# Sheet1.net
KiCad netlist of a schematic drawn in Altium Designer
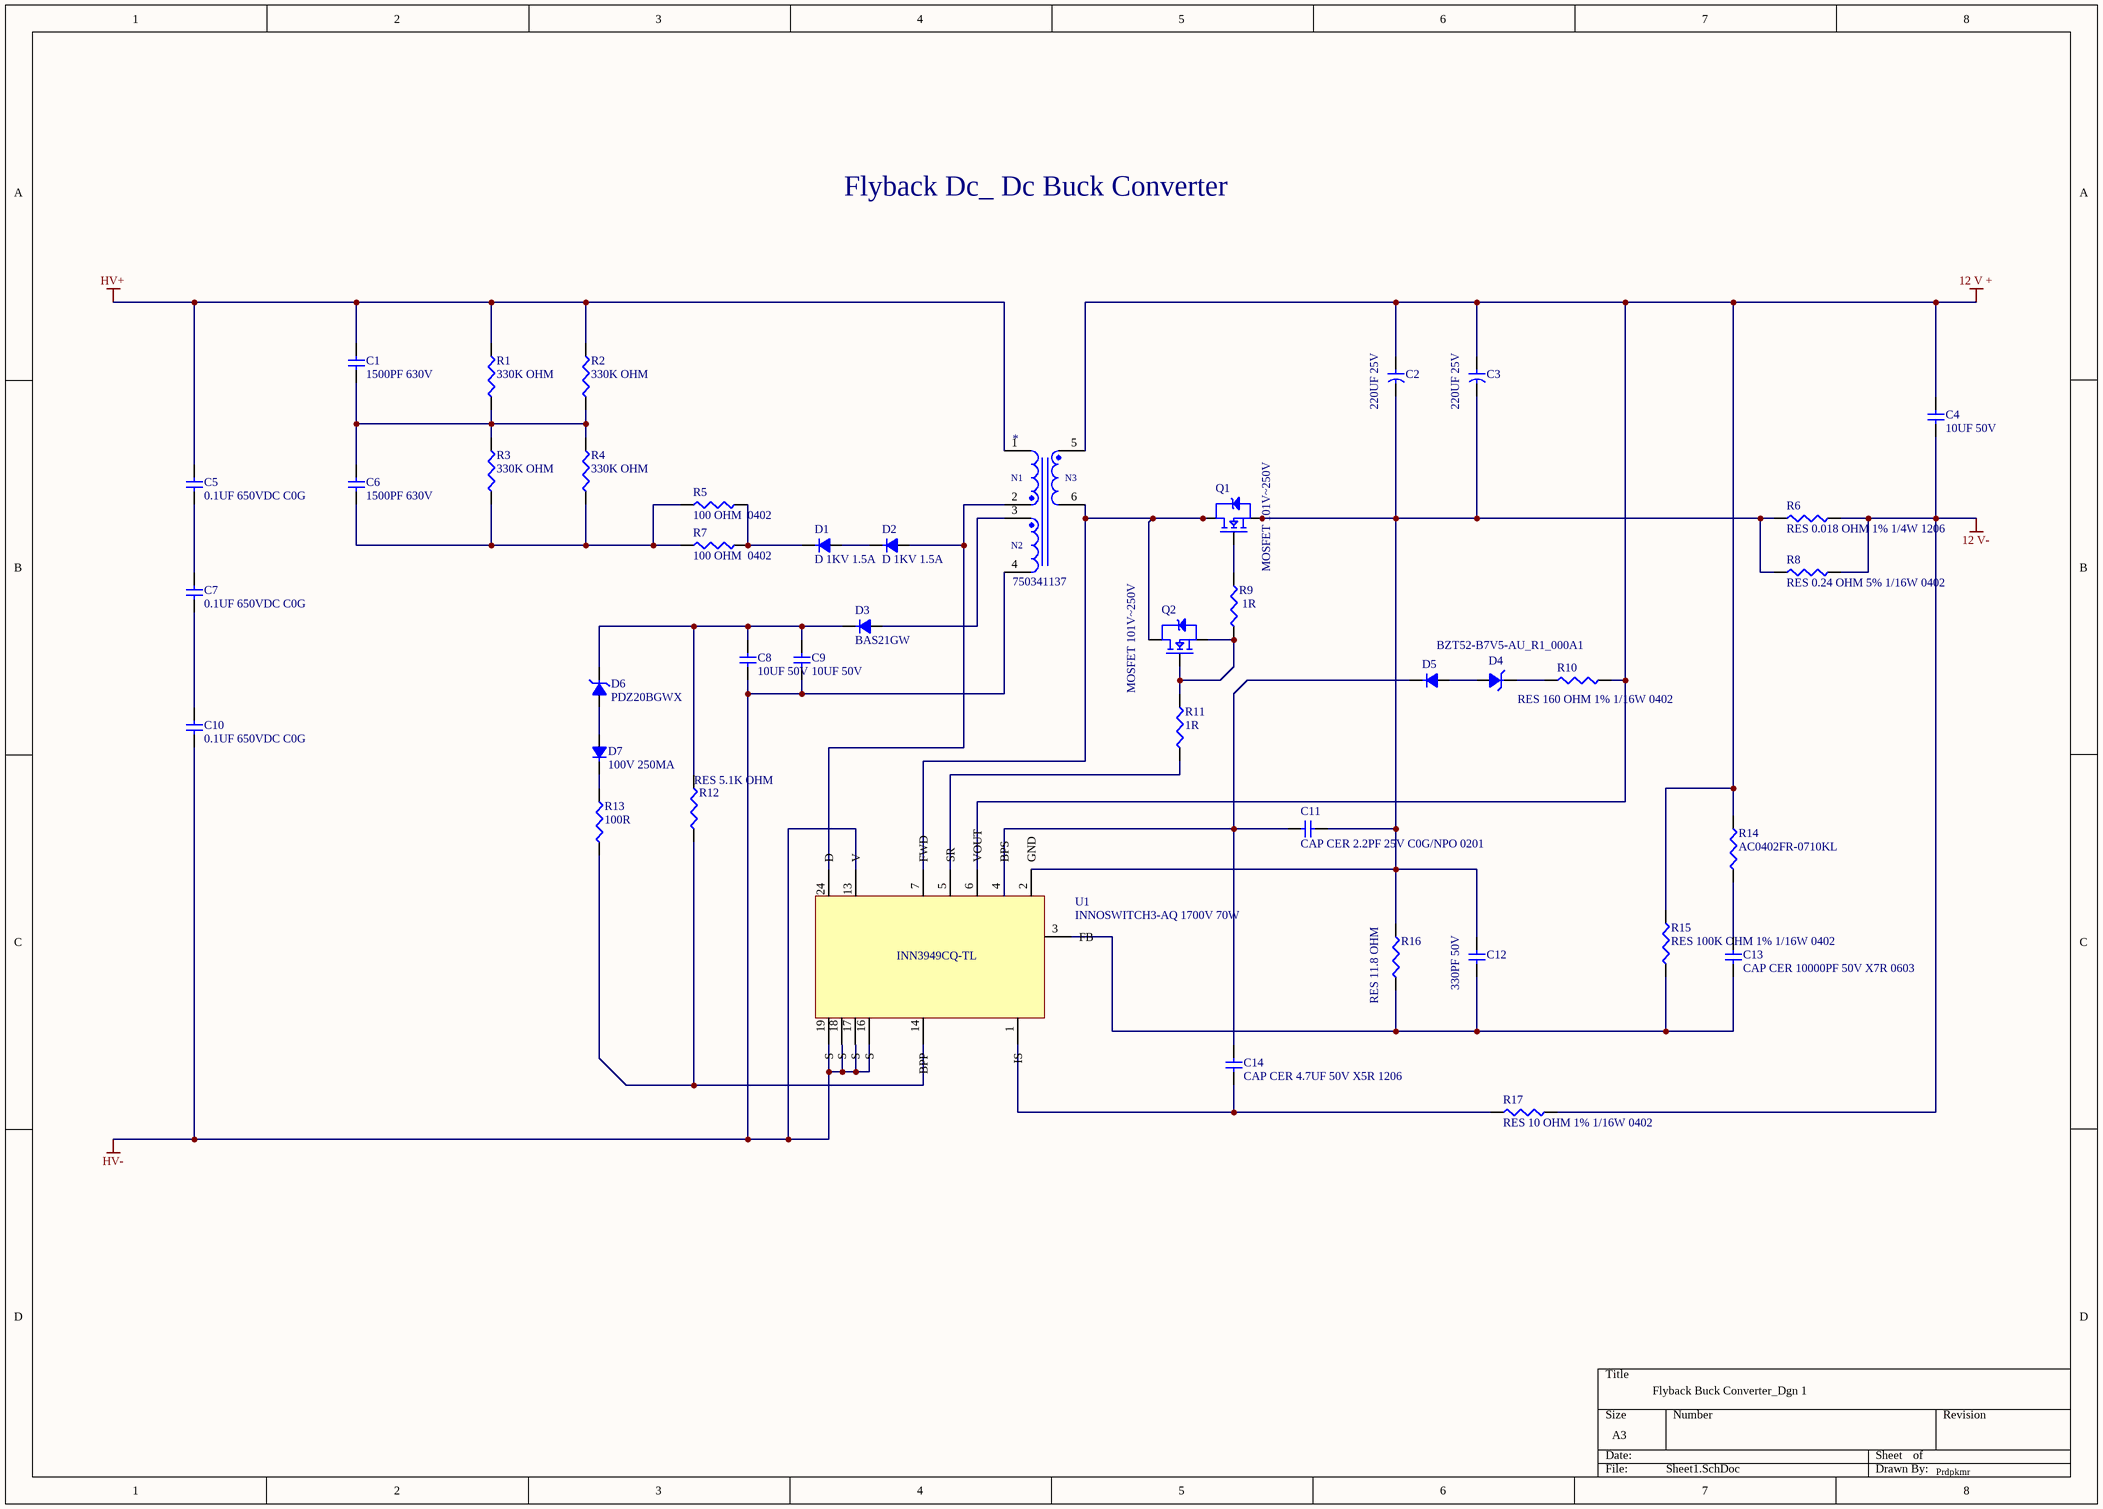
[diagram p0: Sheet1.SchDoc]

(export (version "E")
  (design (tool "Eeschema 10.0.6"))
  (components
    (comp (ref "*")
      (value "750341137")
      (footprint "ERI25/10/18_250-1446")
      (description "Transformer 480UH SMD")
      (fields (field (name "MANUFACTURER") "Wurth Electronics"))
      (libsource (lib "Schlib1") (part "750341137"))
    )
    (comp (ref "C1")
      (value "1500PF 630V")
      (description "1500 pF ±5% 630V Ceramic Capacitor C0G, NP0 1206 (3216 Metric)")
      (fields
        (field (name "MANUFACTURER") "TDK")
        (field (name "MANUFACTURER PART NUMBER") "CGA5H4C0G2J152J115AA")
      )
      (libsource (lib "Schlib1") (part "CGA5H4C0G2J152J115AA"))
    )
    (comp (ref "C2")
      (value "220UF 25V")
      (description "220 µF 25 V Aluminum - Polymer Capacitors Radial, Can - SMD 15mOhm 2000 Hrs @ 105°C")
      (fields
        (field (name "MANUFACTURER") "Wurth Electronics")
        (field (name "MANUFACTURER PART NUMBER") "875075561008")
      )
      (libsource (lib "Schlib1") (part "875075561008"))
    )
    (comp (ref "C3")
      (value "220UF 25V")
      (description "220 µF 25 V Aluminum - Polymer Capacitors Radial, Can - SMD 15mOhm 2000 Hrs @ 105°C")
      (fields
        (field (name "MANUFACTURER") "Wurth Electronics")
        (field (name "MANUFACTURER PART NUMBER") "875075561008")
      )
      (libsource (lib "Schlib1") (part "875075561008"))
    )
    (comp (ref "C4")
      (value "10UF 50V")
      (description "10 µF -20%, +80% 50V Ceramic Capacitor Y5V (F) 1210 (3225 Metric)")
      (fields
        (field (name "MANUFACTURER") "Yageo")
        (field (name "MANUFACTURER PART NUMBER") "CC1210ZKY5V9BB106")
      )
      (libsource (lib "Schlib1") (part "CC1210ZKY5V9BB106"))
    )
    (comp (ref "C5")
      (value "0.1UF 650VDC C0G")
      (description "0.1 µF ±10% 650V Ceramic Capacitor C0G, NP0 2220 (5750 Metric)")
      (fields
        (field (name "MANUFACTURER") "KEMET")
        (field (name "MANUFACTURER PART NUMBER") "CKC21C104KWGACAUTO")
      )
      (libsource (lib "Schlib1") (part "CKC21C104KWGACAUTO"))
    )
    (comp (ref "C6")
      (value "1500PF 630V")
      (description "1500 pF ±5% 630V Ceramic Capacitor C0G, NP0 1206 (3216 Metric)")
      (fields
        (field (name "MANUFACTURER") "TDK")
        (field (name "MANUFACTURER PART NUMBER") "CGA5H4C0G2J152J115AA")
      )
      (libsource (lib "Schlib1") (part "CGA5H4C0G2J152J115AA"))
    )
    (comp (ref "C7")
      (value "0.1UF 650VDC C0G")
      (description "0.1 µF ±10% 650V Ceramic Capacitor C0G, NP0 2220 (5750 Metric)")
      (fields
        (field (name "MANUFACTURER") "KEMET")
        (field (name "MANUFACTURER PART NUMBER") "CKC21C104KWGACAUTO")
      )
      (libsource (lib "Schlib1") (part "CKC21C104KWGACAUTO"))
    )
    (comp (ref "C8")
      (value "10UF 50V")
      (description "10 µF -20%, +80% 50V Ceramic Capacitor Y5V (F) 1210 (3225 Metric)")
      (fields
        (field (name "MANUFACTURER") "Yageo")
        (field (name "MANUFACTURER PART NUMBER") "CC1210ZKY5V9BB106")
      )
      (libsource (lib "Schlib1") (part "CC1210ZKY5V9BB106"))
    )
    (comp (ref "C9")
      (value "10UF 50V")
      (description "10 µF -20%, +80% 50V Ceramic Capacitor Y5V (F) 1210 (3225 Metric)")
      (fields
        (field (name "MANUFACTURER") "Yageo")
        (field (name "MANUFACTURER PART NUMBER") "CC1210ZKY5V9BB106")
      )
      (libsource (lib "Schlib1") (part "CC1210ZKY5V9BB106"))
    )
    (comp (ref "C10")
      (value "0.1UF 650VDC C0G")
      (description "0.1 µF ±10% 650V Ceramic Capacitor C0G, NP0 2220 (5750 Metric)")
      (fields
        (field (name "MANUFACTURER") "KEMET")
        (field (name "MANUFACTURER PART NUMBER") "CKC21C104KWGACAUTO")
      )
      (libsource (lib "Schlib1") (part "CKC21C104KWGACAUTO"))
    )
    (comp (ref "C11")
      (value "CAP CER 2.2PF 25V C0G/NPO 0201")
      (description "2.2 pF ±0.25pF 25V Ceramic Capacitor C0G, NP0 0201 (0603 Metric)")
      (fields
        (field (name "MANUFACTURER") "Yageo")
        (field (name "MANUFACTURER PART NUMBER") "CC0201CRNPO8BN2R2")
      )
      (libsource (lib "Schlib1") (part "CC0201CRNPO8BN2R2"))
    )
    (comp (ref "C12")
      (value "330PF 50V")
      (description "330 pF ±10% 50V Ceramic Capacitor X7R 0402 (1005 Metric)")
      (fields
        (field (name "MANUFACTURER") "Yageo")
        (field (name "MANUFACTURER PART NUMBER") "CC0402KRX7R9BB331")
      )
      (libsource (lib "Schlib1") (part "CC0402KRX7R9BB331"))
    )
    (comp (ref "C13")
      (value "CAP CER 10000PF 50V X7R 0603")
      (description "10000 pF ±10% 50V Ceramic Capacitor X7R 0603 (1608 Metric)")
      (fields
        (field (name "MANUFACTURER") "Yageo")
        (field (name "MANUFACTURER PART NUMBER") "CC0603KRX7R9BB103")
      )
      (libsource (lib "Schlib1") (part "CC0603KRX7R9BB103"))
    )
    (comp (ref "C14")
      (value "CAP CER 4.7UF 50V X5R 1206")
      (description "4.7 µF ±10% 50V Ceramic Capacitor X5R 1206 (3216 Metric)")
      (fields
        (field (name "MANUFACTURER") "Yageo")
        (field (name "MANUFACTURER PART NUMBER") "CC1206KKX5R9BB475")
      )
      (libsource (lib "Schlib1") (part "CC1206KKX5R9BB475"))
    )
    (comp (ref "D1")
      (value "D 1KV 1.5A")
      (description "Diode 1000 V 1.5A Surface Mount DO-214AC (SMA)")
      (fields
        (field (name "MANUFACTURER") "Vishay")
        (field (name "MANUFACTURER PART NUMBER") "BYG23MHE3_A/I")
      )
      (libsource (lib "Schlib1") (part "BYG23MHE3_A/I"))
    )
    (comp (ref "D2")
      (value "D 1KV 1.5A")
      (description "Diode 1000 V 1.5A Surface Mount DO-214AC (SMA)")
      (fields
        (field (name "MANUFACTURER") "Vishay")
        (field (name "MANUFACTURER PART NUMBER") "BYG23MHE3_A/I")
      )
      (libsource (lib "Schlib1") (part "BYG23MHE3_A/I"))
    )
    (comp (ref "D3")
      (value "BAS21GW")
      (description "Diode 200 V 225mA Surface Mount SOD-123")
      (fields (field (name "MANUFACTURER") "Nexperia") (field (name "MANUFACTURER PART NUMBER") "BAS21GWX"))
      (libsource (lib "Schlib1") (part "BAS21GWX"))
    )
    (comp (ref "D4")
      (value "BZT52-B7V5-AU_R1_000A1")
      (description "Zener Diode 7.5 V 410 mW ±2% Surface Mount SOD-123")
      (fields (field (name "MANUFACTURER") "Panjit"))
      (libsource (lib "Schlib1") (part "BZT52-B7V5-AU_R1_000A1"))
    )
    (comp (ref "D5")
      (value "~")
      (description "Diode 100 V 250mA Surface Mount SOD-323F")
      (fields (field (name "MANUFACTURER") "Nexperia") (field (name "MANUFACTURER PART NUMBER") "BAS16J,115"))
      (libsource (lib "Schlib1") (part "BAS16J,115"))
    )
    (comp (ref "D6")
      (value "PDZ20BGWX")
      (description "DIODE ZENER 20V 365MW SOD123")
      (fields (field (name "MANUFACTURER") "Nexperia"))
      (libsource (lib "Schlib1") (part "PDZ20BGWX"))
    )
    (comp (ref "D7")
      (value "100V 250MA")
      (description "Diode 100 V 250mA Surface Mount SOD-323F")
      (fields (field (name "MANUFACTURER") "Nexperia") (field (name "MANUFACTURER PART NUMBER") "BAS16J,115"))
      (libsource (lib "Schlib1") (part "BAS16J,115"))
    )
    (comp (ref "Q1")
      (value "MOSFET 101V~250V")
      (fields
        (field (name "MANUFACTURER") "Diodes")
        (field (name "MANUFACTURER PART NUMBER") "DMTH15H017LPSWQ-13")
      )
      (libsource (lib "Schlib1") (part "DMTH15H017LPSWQ-13"))
    )
    (comp (ref "Q2")
      (value "MOSFET 101V~250V")
      (fields
        (field (name "MANUFACTURER") "Diodes")
        (field (name "MANUFACTURER PART NUMBER") "DMTH15H017LPSWQ-13")
      )
      (libsource (lib "Schlib1") (part "DMTH15H017LPSWQ-13"))
    )
    (comp (ref "R1")
      (value "330K OHM")
      (description "330 kOhms ±1% 0.35W Chip Resistor 1210 (3225 Metric) High Voltage Thick Film")
      (fields
        (field (name "MANUFACTURER") "Vishay")
        (field (name "MANUFACTURER PART NUMBER") "CRMV1210AF330KFKEF")
      )
      (libsource (lib "Schlib1") (part "CRMV1210AF330KFKEF"))
    )
    (comp (ref "R2")
      (value "330K OHM")
      (description "330 kOhms ±1% 0.35W Chip Resistor 1210 (3225 Metric) High Voltage Thick Film")
      (fields
        (field (name "MANUFACTURER") "Vishay")
        (field (name "MANUFACTURER PART NUMBER") "CRMV1210AF330KFKEF")
      )
      (libsource (lib "Schlib1") (part "CRMV1210AF330KFKEF"))
    )
    (comp (ref "R3")
      (value "330K OHM")
      (description "330 kOhms ±1% 0.35W Chip Resistor 1210 (3225 Metric) High Voltage Thick Film")
      (fields
        (field (name "MANUFACTURER") "Vishay")
        (field (name "MANUFACTURER PART NUMBER") "CRMV1210AF330KFKEF")
      )
      (libsource (lib "Schlib1") (part "CRMV1210AF330KFKEF"))
    )
    (comp (ref "R4")
      (value "330K OHM")
      (description "330 kOhms ±1% 0.35W Chip Resistor 1210 (3225 Metric) High Voltage Thick Film")
      (fields
        (field (name "MANUFACTURER") "Vishay")
        (field (name "MANUFACTURER PART NUMBER") "CRMV1210AF330KFKEF")
      )
      (libsource (lib "Schlib1") (part "CRMV1210AF330KFKEF"))
    )
    (comp (ref "R5")
      (value "100 OHM  0402")
      (description "100 Ohms ±1% 0.05W, 1/20W Chip Resistor 0402 (1005 Metric) Military Thick Film")
      (fields
        (field (name "MANUFACTURER") "Vishay Dale")
        (field (name "MANUFACTURER PART NUMBER") "M55342K11B100DRS3")
      )
      (libsource (lib "Schlib1") (part "M55342K11B100DRS3"))
    )
    (comp (ref "R6")
      (value "RES 0.018 OHM 1% 1/4W 1206")
      (description "Res Thick Film 1206 0.018 Ohm 1% 1/4W ±1500ppm/°C Molded SMD SMD Paper T/R")
      (fields
        (field (name "MANUFACTURER") "Yageo")
        (field (name "MANUFACTURER PART NUMBER") "RL1206FR-070R018L")
      )
      (libsource (lib "Schlib1") (part "RL1206FR-070R018L"))
    )
    (comp (ref "R7")
      (value "100 OHM  0402")
      (description "100 Ohms ±1% 0.05W, 1/20W Chip Resistor 0402 (1005 Metric) Military Thick Film")
      (fields
        (field (name "MANUFACTURER") "Vishay Dale")
        (field (name "MANUFACTURER PART NUMBER") "M55342K11B100DRS3")
      )
      (libsource (lib "Schlib1") (part "M55342K11B100DRS3"))
    )
    (comp (ref "R8")
      (value "RES 0.24 OHM 5% 1/16W 0402")
      (description "Current Sensor-Low TCR Chip Resistor Thick Film 0402 240mOhm 5% Paper T/R")
      (fields
        (field (name "MANUFACTURER") "Yageo")
        (field (name "MANUFACTURER PART NUMBER") "PT0402JR-070R24L")
      )
      (libsource (lib "Schlib1") (part "PT0402JR-070R24L"))
    )
    (comp (ref "R9")
      (value "1R")
      (fields
        (field (name "MANUFACTURER") "Bourns")
        (field (name "MANUFACTURER PART NUMBER") "CR0402AF/-1R00GAS")
        (field (name "TOLERANCE") "1%")
      )
      (libsource (lib "Schlib1") (part "CR0402AF/-1R00GAS"))
    )
    (comp (ref "R10")
      (value "RES 160 OHM 1% 1/16W 0402")
      (description "SMD Chip Resistor, 160 Ohm, ï¿½ 1%, 63 mW, 0402 [1005 Metric], Thick Film, General Purpose")
      (fields
        (field (name "MANUFACTURER") "Yageo")
        (field (name "MANUFACTURER PART NUMBER") "RC0402FR-07160RL")
      )
      (libsource (lib "Schlib1") (part "RC0402FR-07160RL"))
    )
    (comp (ref "R11")
      (value "1R")
      (fields
        (field (name "MANUFACTURER") "Bourns")
        (field (name "MANUFACTURER PART NUMBER") "CR0402AF/-1R00GAS")
        (field (name "TOLERANCE") "1%")
      )
      (libsource (lib "Schlib1") (part "CR0402AF/-1R00GAS"))
    )
    (comp (ref "R12")
      (value "RES 5.1K OHM")
      (description "5.1 kOhms ±1% 0.063W, 1/16W Chip Resistor 0402 (1005 Metric) Moisture Resistant Thick Film")
      (fields
        (field (name "MANUFACTURER") "Yageo")
        (field (name "MANUFACTURER PART NUMBER") "RC0402FR-075K1L")
      )
      (libsource (lib "Schlib1") (part "RC0402FR-075K1L"))
    )
    (comp (ref "R13")
      (value "100R")
      (description "100 Ohms ±0.1% 0.063W, 1/16W Chip Resistor 0402 (1005 Metric) Thin Film")
      (fields
        (field (name "MANUFACTURER") "Yageo")
        (field (name "MANUFACTURER PART NUMBER") "RT0402BRD07100RL")
      )
      (libsource (lib "Schlib1") (part "RT0402BRD07100RL"))
    )
    (comp (ref "R14")
      (value "AC0402FR-0710KL")
      (description "SMD Chip Resistor, 10 kOhm, ï¿½ 1%, 62.5 mW, 0402 [1005 Metric], Thick Film, General Purpose")
      (fields (field (name "MANUFACTURER") "Yageo") (field (name "TOLERANCE") "1%"))
      (libsource (lib "Schlib1") (part "AC0402FR-0710KL"))
    )
    (comp (ref "R15")
      (value "RES 100K OHM 1% 1/16W 0402")
      (description "Res General Purpose Thick Film 0402 100K Ohm 1% 1/16W ±100ppm/°C Molded SMD Paper T/R")
      (fields
        (field (name "MANUFACTURER") "Yageo")
        (field (name "MANUFACTURER PART NUMBER") "RC0402FR-07100KL")
      )
      (libsource (lib "Schlib1") (part "RC0402FR-07100KL"))
    )
    (comp (ref "R16")
      (value "RES 11.8 OHM")
      (description "Res Thick Film 0402 11.8 Ohm 1% 0.063W(1/16W) ±100ppm/C Pad SMD T/R")
      (fields
        (field (name "MANUFACTURER") "Yageo")
        (field (name "MANUFACTURER PART NUMBER") "RC0402FR-0711R8L")
      )
      (libsource (lib "Schlib1") (part "RC0402FR-0711R8L"))
    )
    (comp (ref "R17")
      (value "RES 10 OHM 1% 1/16W 0402")
      (description "Res Thick Film 0402 11.8 Ohm 1% 0.063W(1/16W) ±100ppm/C Pad SMD T/R")
      (fields
        (field (name "MANUFACTURER") "Yageo")
        (field (name "MANUFACTURER PART NUMBER") "RC0402FR-0710RL")
      )
      (libsource (lib "Schlib1") (part "RC0402FR-0710RL"))
    )
    (comp (ref "U1")
      (value "INNOSWITCH3-AQ 1700V 70W")
      (description "Ac-Dc Conv, Flyback, -40 To 150Deg C Rohs Compliant: Yes ¦Power Integrations INN3949CQ-TL")
      (fields
        (field (name "MANUFACTURER") "Power Integrations")
        (field (name "MANUFACTURER PART NUMBER") "INN3949CQ-TL")
      )
      (libsource (lib "Schlib1") (part "INN3949CQ-TL"))
    )
  )
  (nets
    (net (code "1") (name "12 V +") (class "Default")
      (node (ref "*") (pin "5") (pinfunction "5_5") (pintype "passive"))
      (node (ref "C2") (pin "1") (pinfunction "1_1") (pintype "passive"))
      (node (ref "C3") (pin "1") (pinfunction "1_1") (pintype "passive"))
      (node (ref "C4") (pin "2") (pinfunction "_2_2") (pintype "passive"))
      (node (ref "R10") (pin "2") (pinfunction "2_2") (pintype "passive"))
      (node (ref "R14") (pin "2") (pinfunction "2_2") (pintype "passive"))
      (node (ref "R15") (pin "2") (pinfunction "2_2") (pintype "passive"))
    )
    (net (code "2") (name "12 V-") (class "Default")
      (node (ref "C4") (pin "1") (pinfunction "1_1") (pintype "passive"))
      (node (ref "R17") (pin "2") (pinfunction "2_2") (pintype "passive"))
      (node (ref "R6") (pin "2") (pinfunction "2_2") (pintype "passive"))
      (node (ref "R8") (pin "2") (pinfunction "2_2") (pintype "passive"))
    )
    (net (code "3") (name "HV+") (class "Default")
      (node (ref "*") (pin "1") (pinfunction "1_1") (pintype "passive"))
      (node (ref "C1") (pin "2") (pinfunction "_2_2") (pintype "passive"))
      (node (ref "C5") (pin "2") (pinfunction "_2_2") (pintype "passive"))
      (node (ref "R1") (pin "2") (pinfunction "2_2") (pintype "passive"))
      (node (ref "R2") (pin "2") (pinfunction "2_2") (pintype "passive"))
    )
    (net (code "4") (name "HV-") (class "Default")
      (node (ref "*") (pin "4") (pinfunction "4_4") (pintype "passive"))
      (node (ref "C10") (pin "1") (pinfunction "1_1") (pintype "passive"))
      (node (ref "C8") (pin "1") (pinfunction "1_1") (pintype "passive"))
      (node (ref "C9") (pin "1") (pinfunction "1_1") (pintype "passive"))
    )
    (net (code "5") (name "Net-(*-Pad2)") (class "Default")
      (node (ref "*") (pin "2") (pinfunction "2_2") (pintype "passive"))
      (node (ref "D2") (pin "1") (pinfunction "1_1") (pintype "passive"))
    )
    (net (code "6") (name "Net-(*-Pad3)") (class "Default")
      (node (ref "*") (pin "3") (pinfunction "3_3") (pintype "passive"))
      (node (ref "D3") (pin "1") (pinfunction "1_1") (pintype "passive"))
    )
    (net (code "7") (name "Net-(*-Pad6)") (class "Default")
      (node (ref "*") (pin "6") (pinfunction "6_6") (pintype "passive"))
      (node (ref "Q1") (pin "2") (pinfunction "2_2") (pintype "passive"))
      (node (ref "Q2") (pin "2") (pinfunction "2_2") (pintype "passive"))
    )
    (net (code "8") (name "Net-(C6-Pad1)") (class "Default")
      (node (ref "C6") (pin "1") (pinfunction "1_1") (pintype "passive"))
      (node (ref "R3") (pin "1") (pinfunction "1_1") (pintype "passive"))
      (node (ref "R4") (pin "1") (pinfunction "1_1") (pintype "passive"))
      (node (ref "R5") (pin "1") (pinfunction "1_1") (pintype "passive"))
      (node (ref "R7") (pin "1") (pinfunction "1_1") (pintype "passive"))
    )
    (net (code "9") (name "Net-(C6-_2)") (class "Default")
      (node (ref "C1") (pin "1") (pinfunction "1_1") (pintype "passive"))
      (node (ref "C6") (pin "2") (pinfunction "_2_2") (pintype "passive"))
      (node (ref "R1") (pin "1") (pinfunction "1_1") (pintype "passive"))
      (node (ref "R2") (pin "1") (pinfunction "1_1") (pintype "passive"))
      (node (ref "R3") (pin "2") (pinfunction "2_2") (pintype "passive"))
      (node (ref "R4") (pin "2") (pinfunction "2_2") (pintype "passive"))
    )
    (net (code "10") (name "Net-(C7-_2)") (class "Default")
      (node (ref "C5") (pin "1") (pinfunction "1_1") (pintype "passive"))
      (node (ref "C7") (pin "2") (pinfunction "_2_2") (pintype "passive"))
    )
    (net (code "11") (name "Net-(C8-_2)") (class "Default")
      (node (ref "C8") (pin "2") (pinfunction "_2_2") (pintype "passive"))
      (node (ref "C9") (pin "2") (pinfunction "_2_2") (pintype "passive"))
      (node (ref "D3") (pin "2") (pinfunction "2_2") (pintype "passive"))
      (node (ref "D6") (pin "2") (pinfunction "2_2") (pintype "passive"))
      (node (ref "R12") (pin "2") (pinfunction "2_2") (pintype "passive"))
    )
    (net (code "12") (name "Net-(C10-_2)") (class "Default")
      (node (ref "C10") (pin "2") (pinfunction "_2_2") (pintype "passive"))
      (node (ref "C7") (pin "1") (pinfunction "1_1") (pintype "passive"))
    )
    (net (code "13") (name "Net-(C11-_2)") (class "Default")
      (node (ref "C11") (pin "2") (pinfunction "_2_2") (pintype "passive"))
      (node (ref "C12") (pin "2") (pinfunction "_2_2") (pintype "passive"))
      (node (ref "C2") (pin "2") (pinfunction "_2_2") (pintype "passive"))
      (node (ref "C3") (pin "2") (pinfunction "_2_2") (pintype "passive"))
      (node (ref "Q1") (pin "3") (pinfunction "3_3") (pintype "passive"))
      (node (ref "R16") (pin "2") (pinfunction "2_2") (pintype "passive"))
      (node (ref "R6") (pin "1") (pinfunction "1_1") (pintype "passive"))
      (node (ref "R8") (pin "1") (pinfunction "1_1") (pintype "passive"))
    )
    (net (code "14") (name "Net-(C12-Pad1)") (class "Default")
      (node (ref "C12") (pin "1") (pinfunction "1_1") (pintype "passive"))
      (node (ref "C13") (pin "1") (pinfunction "1_1") (pintype "passive"))
      (node (ref "R15") (pin "1") (pinfunction "1_1") (pintype "passive"))
      (node (ref "R16") (pin "1") (pinfunction "1_1") (pintype "passive"))
    )
    (net (code "15") (name "Net-(C13-_2)") (class "Default")
      (node (ref "C13") (pin "2") (pinfunction "_2_2") (pintype "passive"))
      (node (ref "R14") (pin "1") (pinfunction "1_1") (pintype "passive"))
    )
    (net (code "16") (name "Net-(C14-Pad1)") (class "Default")
      (node (ref "C14") (pin "1") (pinfunction "1_1") (pintype "passive"))
      (node (ref "R17") (pin "1") (pinfunction "1_1") (pintype "passive"))
    )
    (net (code "17") (name "Net-(C14-_2)") (class "Default")
      (node (ref "C11") (pin "1") (pinfunction "1_1") (pintype "passive"))
      (node (ref "C14") (pin "2") (pinfunction "_2_2") (pintype "passive"))
      (node (ref "D5") (pin "2") (pinfunction "2_2") (pintype "passive"))
      (node (ref "U1") (pin "4") (pinfunction "BPS_4") (pintype "passive"))
    )
    (net (code "18") (name "Net-(D1-Pad1)") (class "Default")
      (node (ref "D1") (pin "1") (pinfunction "1_1") (pintype "passive"))
      (node (ref "D2") (pin "2") (pinfunction "2_2") (pintype "passive"))
    )
    (net (code "19") (name "Net-(D1-Pad2)") (class "Default")
      (node (ref "D1") (pin "2") (pinfunction "2_2") (pintype "passive"))
      (node (ref "R5") (pin "2") (pinfunction "2_2") (pintype "passive"))
      (node (ref "R7") (pin "2") (pinfunction "2_2") (pintype "passive"))
    )
    (net (code "20") (name "Net-(D4-Pad1)") (class "Default")
      (node (ref "D4") (pin "1") (pinfunction "1_1") (pintype "passive"))
      (node (ref "D5") (pin "1") (pinfunction "1_1") (pintype "passive"))
    )
    (net (code "21") (name "Net-(D4-Pad2)") (class "Default")
      (node (ref "D4") (pin "2") (pinfunction "2_2") (pintype "passive"))
      (node (ref "R10") (pin "1") (pinfunction "1_1") (pintype "passive"))
    )
    (net (code "22") (name "Net-(D6-Pad1)") (class "Default")
      (node (ref "D6") (pin "1") (pinfunction "1_1") (pintype "passive"))
      (node (ref "D7") (pin "1") (pinfunction "1_1") (pintype "passive"))
    )
    (net (code "23") (name "Net-(D7-Pad2)") (class "Default")
      (node (ref "D7") (pin "2") (pinfunction "2_2") (pintype "passive"))
      (node (ref "R13") (pin "2") (pinfunction "2_2") (pintype "passive"))
    )
    (net (code "24") (name "Net-(Q1-Pad1)") (class "Default")
      (node (ref "Q1") (pin "1") (pinfunction "1_1") (pintype "passive"))
      (node (ref "R9") (pin "2") (pinfunction "2_2") (pintype "passive"))
    )
    (net (code "25") (name "Net-(Q2-Pad1)") (class "Default")
      (node (ref "Q2") (pin "1") (pinfunction "1_1") (pintype "passive"))
      (node (ref "Q2") (pin "3") (pinfunction "3_3") (pintype "passive"))
      (node (ref "R11") (pin "2") (pinfunction "2_2") (pintype "passive"))
      (node (ref "R9") (pin "1") (pinfunction "1_1") (pintype "passive"))
    )
    (net (code "26") (name "Net-(R12-Pad1)") (class "Default")
      (node (ref "R12") (pin "1") (pinfunction "1_1") (pintype "passive"))
      (node (ref "R13") (pin "1") (pinfunction "1_1") (pintype "passive"))
    )
    (net (code "27") (name "unconnected-(R11-Pad1)") (class "Default")
      (node (ref "R11") (pin "1") (pinfunction "1_1") (pintype "passive"))
    )
    (net (code "28") (name "unconnected-(U1-BPP-Pad14)") (class "Default")
      (node (ref "U1") (pin "14") (pinfunction "BPP_14") (pintype "passive"))
    )
    (net (code "29") (name "unconnected-(U1-D-Pad24)") (class "Default")
      (node (ref "U1") (pin "24") (pinfunction "D_24") (pintype "passive"))
    )
    (net (code "30") (name "unconnected-(U1-FB-Pad3)") (class "Default")
      (node (ref "U1") (pin "3") (pinfunction "FB_3") (pintype "passive"))
    )
    (net (code "31") (name "unconnected-(U1-FWD-Pad7)") (class "Default")
      (node (ref "U1") (pin "7") (pinfunction "FWD_7") (pintype "passive"))
    )
    (net (code "32") (name "unconnected-(U1-GND-Pad2)") (class "Default")
      (node (ref "U1") (pin "2") (pinfunction "GND_2") (pintype "passive"))
    )
    (net (code "33") (name "unconnected-(U1-IS-Pad1)") (class "Default")
      (node (ref "U1") (pin "1") (pinfunction "IS_1") (pintype "passive"))
    )
    (net (code "34") (name "unconnected-(U1-S-Pad16)") (class "Default")
      (node (ref "U1") (pin "16") (pinfunction "S_16") (pintype "passive"))
    )
    (net (code "35") (name "unconnected-(U1-S-Pad17)") (class "Default")
      (node (ref "U1") (pin "17") (pinfunction "S_17") (pintype "passive"))
    )
    (net (code "36") (name "unconnected-(U1-S-Pad18)") (class "Default")
      (node (ref "U1") (pin "18") (pinfunction "S_18") (pintype "passive"))
    )
    (net (code "37") (name "unconnected-(U1-S-Pad19)") (class "Default")
      (node (ref "U1") (pin "19") (pinfunction "S_19") (pintype "passive"))
    )
    (net (code "38") (name "unconnected-(U1-SR-Pad5)") (class "Default")
      (node (ref "U1") (pin "5") (pinfunction "SR_5") (pintype "passive"))
    )
    (net (code "39") (name "unconnected-(U1-V-Pad13)") (class "Default")
      (node (ref "U1") (pin "13") (pinfunction "V_13") (pintype "passive"))
    )
    (net (code "40") (name "unconnected-(U1-VOUT-Pad6)") (class "Default")
      (node (ref "U1") (pin "6") (pinfunction "VOUT_6") (pintype "passive"))
    )
  )
)
